# QVGA.net
KiCad netlist of a schematic drawn in Altium Designer
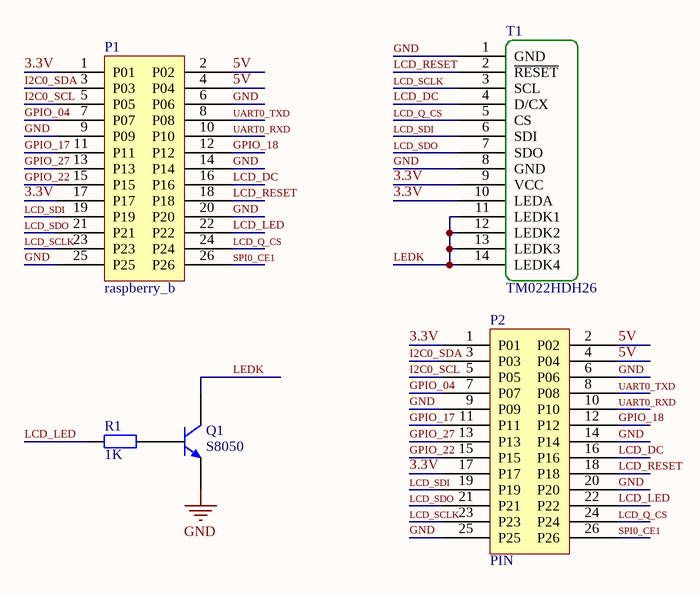
[diagram p0: QVGA.SchDoc]

(export (version "E")
  (design (tool "Eeschema 10.0.6"))
  (components
    (comp (ref "P1")
      (value "raspberry_b")
      (footprint "GPIO13x2")
      (libsource (lib "2.2_TFT") (part "raspberry_b"))
    )
    (comp (ref "P2") (value "PIN") (footprint "GPIO13x2") (libsource (lib "2.2_TFT") (part "raspberry_b")))
    (comp (ref "Q1")
      (value "S8050")
      (footprint "SOT23 - duplicate")
      (libsource (lib "2.2_TFT") (part "S8050"))
    )
    (comp (ref "R1") (value "1K") (footprint "1206") (libsource (lib "2.2_TFT") (part "register")))
    (comp (ref "T1")
      (value "TM022HDH26")
      (footprint "TM022HDH26")
      (description "2.2寸无触摸")
      (libsource (lib "2.2_TFT") (part "TM022HDH26"))
    )
  )
  (nets
    (net (code "1") (name "/3.3V") (class "Default")
      (node (ref "P1") (pin "1") (pinfunction "P01_1") (pintype "passive"))
      (node (ref "P1") (pin "17") (pinfunction "P17_17") (pintype "passive"))
      (node (ref "P2") (pin "1") (pinfunction "P01_1") (pintype "passive"))
      (node (ref "P2") (pin "17") (pinfunction "P17_17") (pintype "passive"))
      (node (ref "T1") (pin "10") (pinfunction "LEDA_10") (pintype "passive"))
      (node (ref "T1") (pin "9") (pinfunction "VCC_9") (pintype "passive"))
    )
    (net (code "2") (name "/5V") (class "Default")
      (node (ref "P1") (pin "2") (pinfunction "P02_2") (pintype "passive"))
      (node (ref "P1") (pin "4") (pinfunction "P04_4") (pintype "passive"))
      (node (ref "P2") (pin "2") (pinfunction "P02_2") (pintype "passive"))
      (node (ref "P2") (pin "4") (pinfunction "P04_4") (pintype "passive"))
    )
    (net (code "3") (name "/GPIO_04") (class "Default")
      (node (ref "P1") (pin "7") (pinfunction "P07_7") (pintype "passive"))
      (node (ref "P2") (pin "7") (pinfunction "P07_7") (pintype "passive"))
    )
    (net (code "4") (name "/GPIO_17") (class "Default")
      (node (ref "P1") (pin "11") (pinfunction "P11_11") (pintype "passive"))
      (node (ref "P2") (pin "11") (pinfunction "P11_11") (pintype "passive"))
    )
    (net (code "5") (name "/GPIO_18") (class "Default")
      (node (ref "P1") (pin "12") (pinfunction "P12_12") (pintype "passive"))
      (node (ref "P2") (pin "12") (pinfunction "P12_12") (pintype "passive"))
    )
    (net (code "6") (name "/GPIO_22") (class "Default")
      (node (ref "P1") (pin "15") (pinfunction "P15_15") (pintype "passive"))
      (node (ref "P2") (pin "15") (pinfunction "P15_15") (pintype "passive"))
    )
    (net (code "7") (name "/GPIO_27") (class "Default")
      (node (ref "P1") (pin "13") (pinfunction "P13_13") (pintype "passive"))
      (node (ref "P2") (pin "13") (pinfunction "P13_13") (pintype "passive"))
    )
    (net (code "8") (name "/I2C0_SCL") (class "Default")
      (node (ref "P1") (pin "5") (pinfunction "P05_5") (pintype "passive"))
      (node (ref "P2") (pin "5") (pinfunction "P05_5") (pintype "passive"))
    )
    (net (code "9") (name "/I2C0_SDA") (class "Default")
      (node (ref "P1") (pin "3") (pinfunction "P03_3") (pintype "passive"))
      (node (ref "P2") (pin "3") (pinfunction "P03_3") (pintype "passive"))
    )
    (net (code "10") (name "/LCD_DC") (class "Default")
      (node (ref "P1") (pin "16") (pinfunction "P16_16") (pintype "passive"))
      (node (ref "P2") (pin "16") (pinfunction "P16_16") (pintype "passive"))
      (node (ref "T1") (pin "4") (pinfunction "D/CX_4") (pintype "passive"))
    )
    (net (code "11") (name "/LCD_LED") (class "Default")
      (node (ref "P1") (pin "22") (pinfunction "P22_22") (pintype "passive"))
      (node (ref "P2") (pin "22") (pinfunction "P22_22") (pintype "passive"))
      (node (ref "R1") (pin "1") (pinfunction "1_1") (pintype "passive"))
    )
    (net (code "12") (name "/LCD_Q_CS") (class "Default")
      (node (ref "P1") (pin "24") (pinfunction "P24_24") (pintype "passive"))
      (node (ref "P2") (pin "24") (pinfunction "P24_24") (pintype "passive"))
      (node (ref "T1") (pin "5") (pinfunction "CS_5") (pintype "passive"))
    )
    (net (code "13") (name "/LCD_RESET") (class "Default")
      (node (ref "P1") (pin "18") (pinfunction "P18_18") (pintype "passive"))
      (node (ref "P2") (pin "18") (pinfunction "P18_18") (pintype "passive"))
      (node (ref "T1") (pin "2") (pinfunction "~{RESET}_2") (pintype "passive"))
    )
    (net (code "14") (name "/LCD_SCLK") (class "Default")
      (node (ref "P1") (pin "23") (pinfunction "P23_23") (pintype "passive"))
      (node (ref "P2") (pin "23") (pinfunction "P23_23") (pintype "passive"))
      (node (ref "T1") (pin "3") (pinfunction "SCL_3") (pintype "passive"))
    )
    (net (code "15") (name "/LCD_SDI") (class "Default")
      (node (ref "P1") (pin "19") (pinfunction "P19_19") (pintype "passive"))
      (node (ref "P2") (pin "19") (pinfunction "P19_19") (pintype "passive"))
      (node (ref "T1") (pin "6") (pinfunction "SDI_6") (pintype "passive"))
    )
    (net (code "16") (name "/LCD_SDO") (class "Default")
      (node (ref "P1") (pin "21") (pinfunction "P21_21") (pintype "passive"))
      (node (ref "P2") (pin "21") (pinfunction "P21_21") (pintype "passive"))
      (node (ref "T1") (pin "7") (pinfunction "SDO_7") (pintype "passive"))
    )
    (net (code "17") (name "/LEDK") (class "Default")
      (node (ref "Q1") (pin "3") (pinfunction "C_3") (pintype "passive"))
      (node (ref "T1") (pin "11") (pinfunction "LEDK1_11") (pintype "passive"))
      (node (ref "T1") (pin "12") (pinfunction "LEDK2_12") (pintype "passive"))
      (node (ref "T1") (pin "13") (pinfunction "LEDK3_13") (pintype "passive"))
      (node (ref "T1") (pin "14") (pinfunction "LEDK4_14") (pintype "passive"))
    )
    (net (code "18") (name "/SPI0_CE1") (class "Default")
      (node (ref "P1") (pin "26") (pinfunction "P26_26") (pintype "passive"))
      (node (ref "P2") (pin "26") (pinfunction "P26_26") (pintype "passive"))
    )
    (net (code "19") (name "/UART0_RXD") (class "Default")
      (node (ref "P1") (pin "10") (pinfunction "P10_10") (pintype "passive"))
      (node (ref "P2") (pin "10") (pinfunction "P10_10") (pintype "passive"))
    )
    (net (code "20") (name "/UART0_TXD") (class "Default")
      (node (ref "P1") (pin "8") (pinfunction "P08_8") (pintype "passive"))
      (node (ref "P2") (pin "8") (pinfunction "P08_8") (pintype "passive"))
    )
    (net (code "21") (name "GND") (class "Default")
      (node (ref "P1") (pin "14") (pinfunction "P14_14") (pintype "passive"))
      (node (ref "P1") (pin "20") (pinfunction "P20_20") (pintype "passive"))
      (node (ref "P1") (pin "25") (pinfunction "P25_25") (pintype "passive"))
      (node (ref "P1") (pin "6") (pinfunction "P06_6") (pintype "passive"))
      (node (ref "P1") (pin "9") (pinfunction "P09_9") (pintype "passive"))
      (node (ref "P2") (pin "14") (pinfunction "P14_14") (pintype "passive"))
      (node (ref "P2") (pin "20") (pinfunction "P20_20") (pintype "passive"))
      (node (ref "P2") (pin "25") (pinfunction "P25_25") (pintype "passive"))
      (node (ref "P2") (pin "6") (pinfunction "P06_6") (pintype "passive"))
      (node (ref "P2") (pin "9") (pinfunction "P09_9") (pintype "passive"))
      (node (ref "Q1") (pin "1") (pinfunction "E_1") (pintype "passive"))
      (node (ref "T1") (pin "1") (pinfunction "GND_1") (pintype "passive"))
      (node (ref "T1") (pin "8") (pinfunction "GND_8") (pintype "passive"))
    )
    (net (code "22") (name "Net-(Q1-B)") (class "Default")
      (node (ref "Q1") (pin "2") (pinfunction "B_2") (pintype "passive"))
      (node (ref "R1") (pin "2") (pinfunction "2_2") (pintype "passive"))
    )
  )
)
